# MotorShield.net
KiCad netlist of a schematic drawn in EAGLE
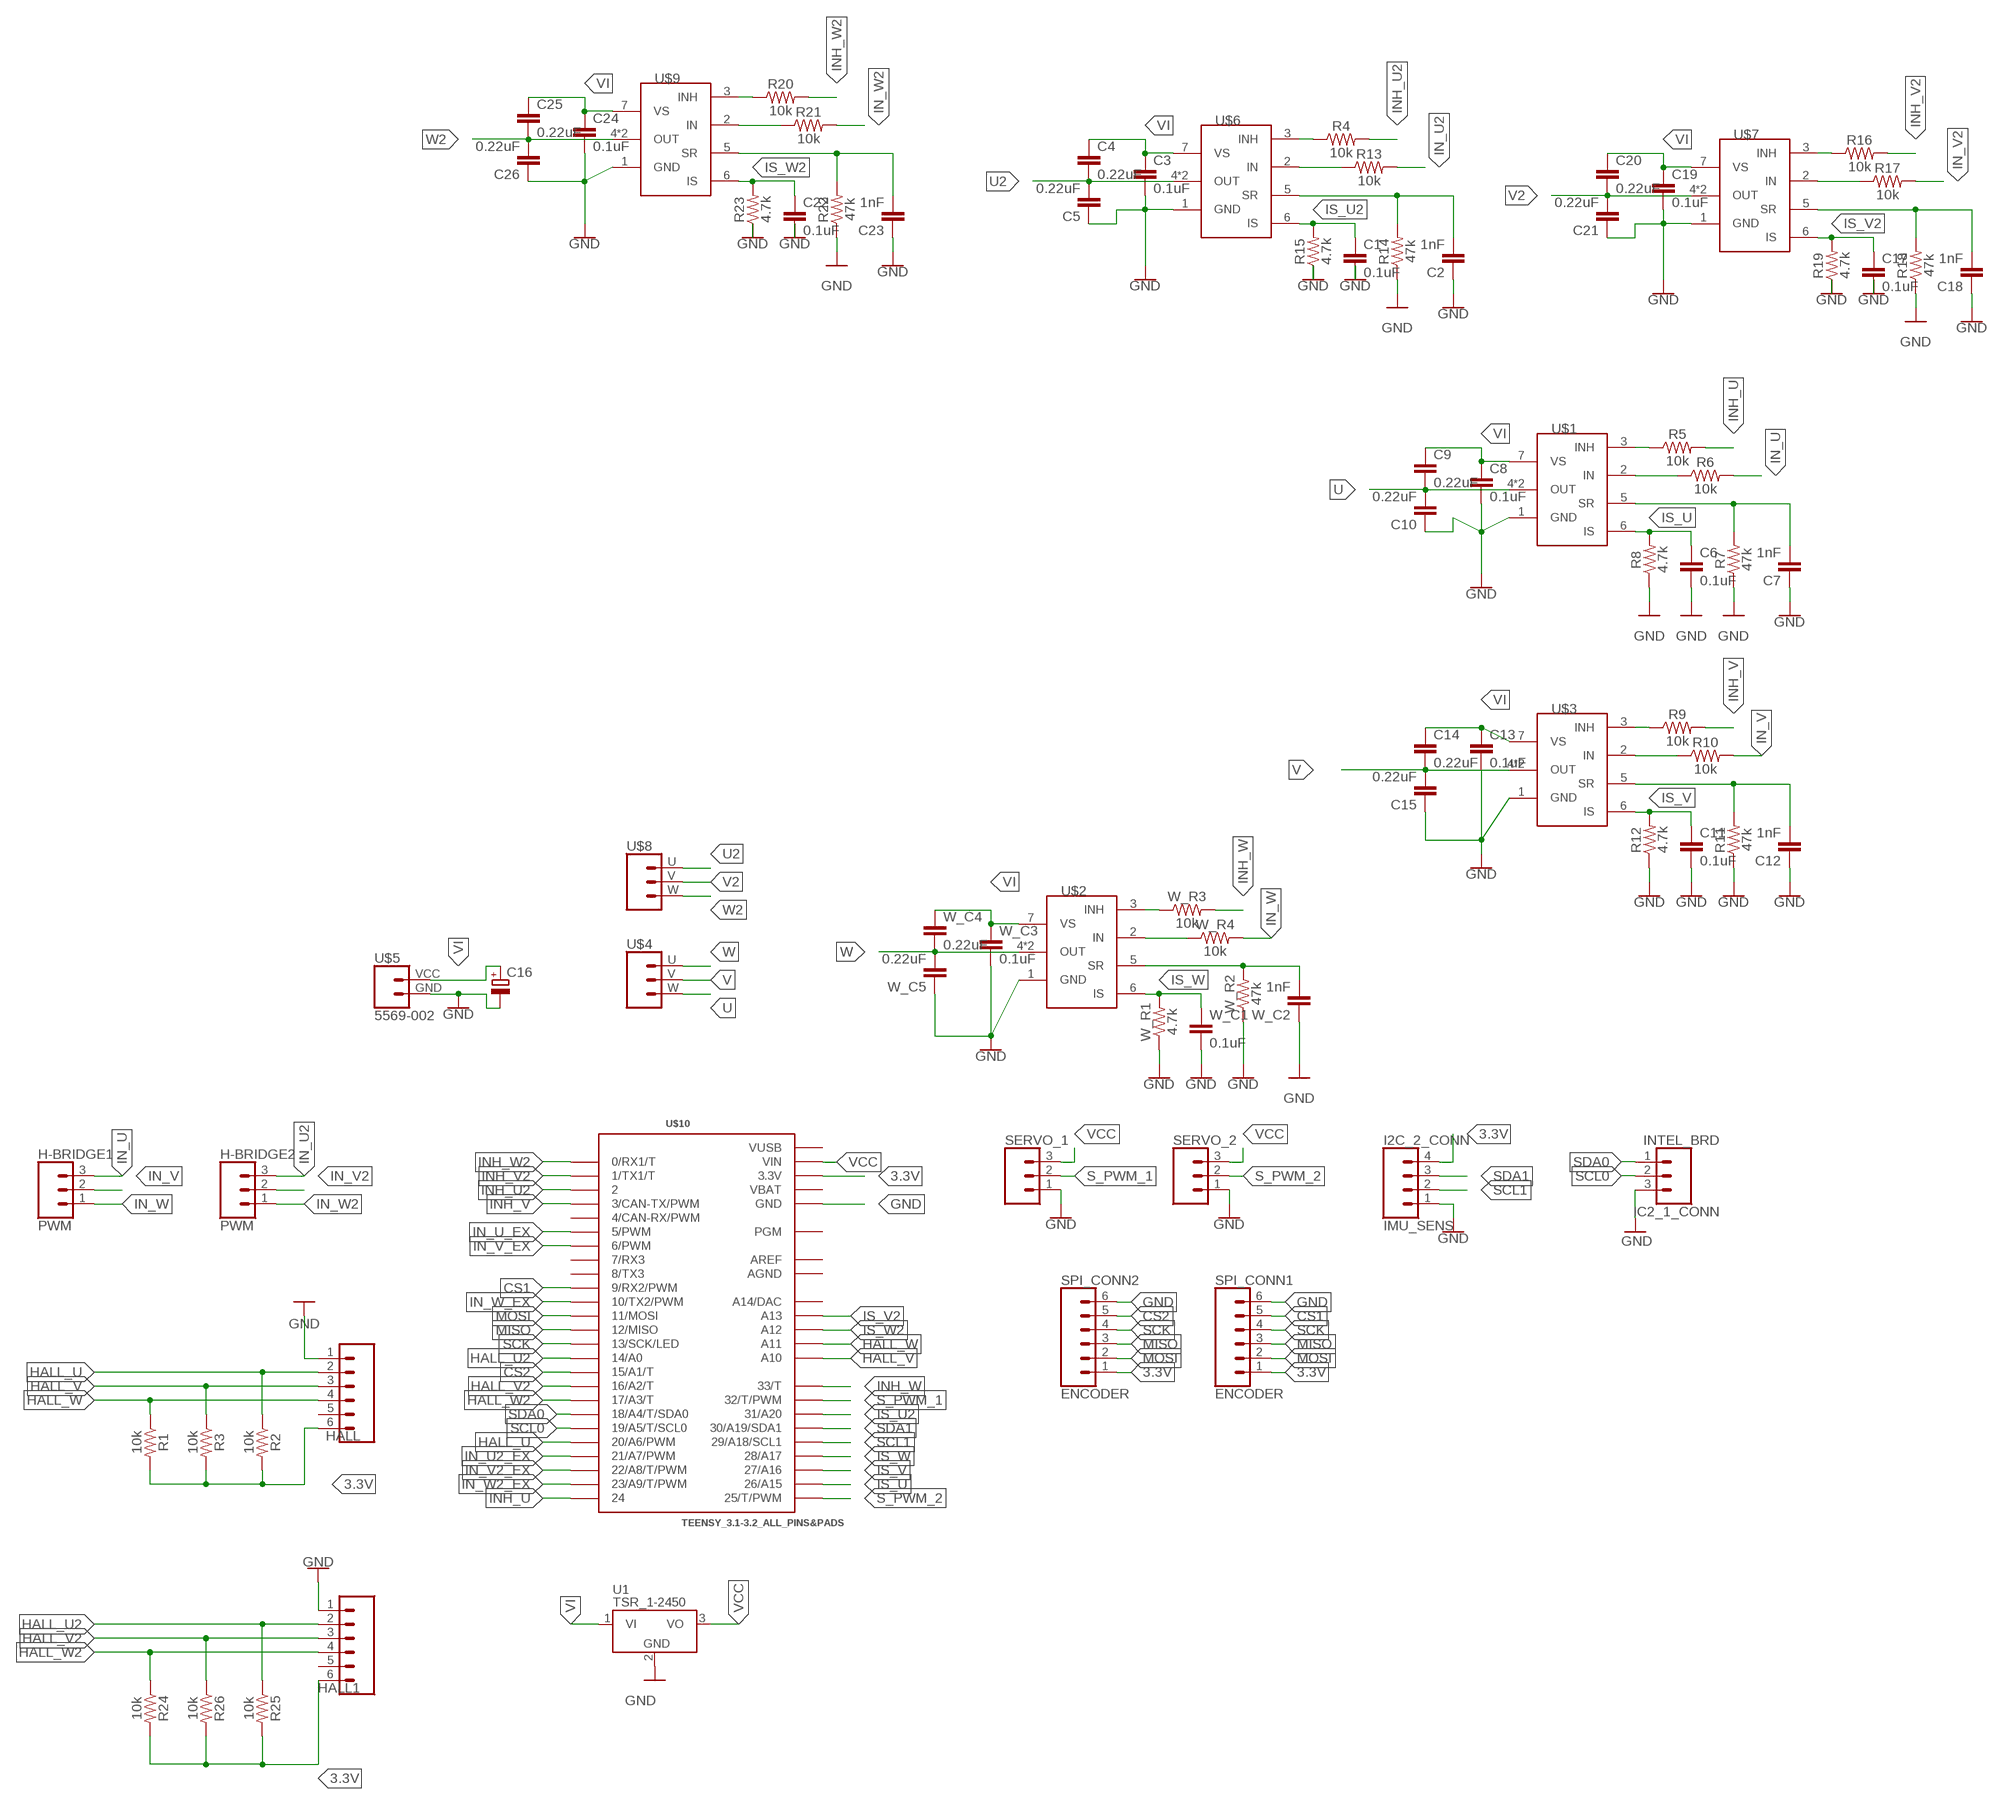
[diagram p0: schematic, sheet 1]

(export (version "E")
  (design (tool "Eeschema 10.0.6"))
  (components
    (comp (ref "C1")
      (value "0.1uF")
      (footprint "eagle-import:0603")
      (libsource (lib "eagle-import") (part "0.1UF-0603-25V-5%"))
    )
    (comp (ref "C2")
      (value "1nF")
      (footprint "eagle-import:0603")
      (libsource (lib "eagle-import") (part "1.0NF/1000PF-0603-50V-10%"))
    )
    (comp (ref "C3")
      (value "0.1uF")
      (footprint "eagle-import:0603")
      (libsource (lib "eagle-import") (part "0.1UF-0603-25V-5%"))
    )
    (comp (ref "C4")
      (value "0.22uF")
      (footprint "eagle-import:0603")
      (libsource (lib "eagle-import") (part "0.22UF-0603-25V-10%"))
    )
    (comp (ref "C5")
      (value "0.22uF")
      (footprint "eagle-import:0603")
      (libsource (lib "eagle-import") (part "0.22UF-0603-25V-10%"))
    )
    (comp (ref "C6")
      (value "0.1uF")
      (footprint "eagle-import:0603")
      (libsource (lib "eagle-import") (part "0.1UF-0603-25V-5%"))
    )
    (comp (ref "C7")
      (value "1nF")
      (footprint "eagle-import:0603")
      (libsource (lib "eagle-import") (part "1.0NF/1000PF-0603-50V-10%"))
    )
    (comp (ref "C8")
      (value "0.1uF")
      (footprint "eagle-import:0603")
      (libsource (lib "eagle-import") (part "0.1UF-0603-25V-5%"))
    )
    (comp (ref "C9")
      (value "0.22uF")
      (footprint "eagle-import:0603")
      (libsource (lib "eagle-import") (part "0.22UF-0603-25V-10%"))
    )
    (comp (ref "C10")
      (value "0.22uF")
      (footprint "eagle-import:0603")
      (libsource (lib "eagle-import") (part "0.22UF-0603-25V-10%"))
    )
    (comp (ref "C11")
      (value "0.1uF")
      (footprint "eagle-import:0603")
      (libsource (lib "eagle-import") (part "0.1UF-0603-25V-5%"))
    )
    (comp (ref "C12")
      (value "1nF")
      (footprint "eagle-import:0603")
      (libsource (lib "eagle-import") (part "1.0NF/1000PF-0603-50V-10%"))
    )
    (comp (ref "C13")
      (value "0.1uF")
      (footprint "eagle-import:0603")
      (libsource (lib "eagle-import") (part "0.1UF-0603-25V-5%"))
    )
    (comp (ref "C14")
      (value "0.22uF")
      (footprint "eagle-import:0603")
      (libsource (lib "eagle-import") (part "0.22UF-0603-25V-10%"))
    )
    (comp (ref "C15")
      (value "0.22uF")
      (footprint "eagle-import:0603")
      (libsource (lib "eagle-import") (part "0.22UF-0603-25V-10%"))
    )
    (comp (ref "C16")
      (value "CPOL-EUE2,5-6E")
      (footprint "eagle-import:E2,5-6E")
      (libsource (lib "eagle-import") (part "CPOL-EUE2,5-6E"))
    )
    (comp (ref "C17")
      (value "0.1uF")
      (footprint "eagle-import:0603")
      (libsource (lib "eagle-import") (part "0.1UF-0603-25V-5%"))
    )
    (comp (ref "C18")
      (value "1nF")
      (footprint "eagle-import:0603")
      (libsource (lib "eagle-import") (part "1.0NF/1000PF-0603-50V-10%"))
    )
    (comp (ref "C19")
      (value "0.1uF")
      (footprint "eagle-import:0603")
      (libsource (lib "eagle-import") (part "0.1UF-0603-25V-5%"))
    )
    (comp (ref "C20")
      (value "0.22uF")
      (footprint "eagle-import:0603")
      (libsource (lib "eagle-import") (part "0.22UF-0603-25V-10%"))
    )
    (comp (ref "C21")
      (value "0.22uF")
      (footprint "eagle-import:0603")
      (libsource (lib "eagle-import") (part "0.22UF-0603-25V-10%"))
    )
    (comp (ref "C22")
      (value "0.1uF")
      (footprint "eagle-import:0603")
      (libsource (lib "eagle-import") (part "0.1UF-0603-25V-5%"))
    )
    (comp (ref "C23")
      (value "1nF")
      (footprint "eagle-import:0603")
      (libsource (lib "eagle-import") (part "1.0NF/1000PF-0603-50V-10%"))
    )
    (comp (ref "C24")
      (value "0.1uF")
      (footprint "eagle-import:0603")
      (libsource (lib "eagle-import") (part "0.1UF-0603-25V-5%"))
    )
    (comp (ref "C25")
      (value "0.22uF")
      (footprint "eagle-import:0603")
      (libsource (lib "eagle-import") (part "0.22UF-0603-25V-10%"))
    )
    (comp (ref "C26")
      (value "0.22uF")
      (footprint "eagle-import:0603")
      (libsource (lib "eagle-import") (part "0.22UF-0603-25V-10%"))
    )
    (comp (ref "H-BRIDGE1")
      (value "PWM")
      (footprint "eagle-import:1X03_NO_SILK")
      (libsource (lib "eagle-import") (part "CONN_031X03_NO_SILK"))
    )
    (comp (ref "H-BRIDGE2")
      (value "PWM")
      (footprint "eagle-import:1X03_NO_SILK")
      (libsource (lib "eagle-import") (part "CONN_031X03_NO_SILK"))
    )
    (comp (ref "HALL")
      (value "CONN_06SMD-1MM")
      (footprint "eagle-import:1X06-1MM")
      (libsource (lib "eagle-import") (part "CONN_06SMD-1MM"))
    )
    (comp (ref "HALL1")
      (value "CONN_06SMD-1MM")
      (footprint "eagle-import:1X06-1MM")
      (libsource (lib "eagle-import") (part "CONN_06SMD-1MM"))
    )
    (comp (ref "I2C_2_CONN")
      (value "IMU_SENS")
      (footprint "eagle-import:1X04_NO_SILK")
      (libsource (lib "eagle-import") (part "CONN_041X04_NO_SILK"))
    )
    (comp (ref "IC2_1_CONN")
      (value "INTEL_BRD")
      (footprint "eagle-import:1X03_NO_SILK")
      (libsource (lib "eagle-import") (part "CONN_031X03_NO_SILK"))
    )
    (comp (ref "R1")
      (value "10k")
      (footprint "eagle-import:0603")
      (libsource (lib "eagle-import") (part "10KOHM-0603-1/10W-1%"))
    )
    (comp (ref "R2")
      (value "10k")
      (footprint "eagle-import:0603")
      (libsource (lib "eagle-import") (part "10KOHM-0603-1/10W-1%"))
    )
    (comp (ref "R3")
      (value "10k")
      (footprint "eagle-import:0603")
      (libsource (lib "eagle-import") (part "10KOHM-0603-1/10W-1%"))
    )
    (comp (ref "R4")
      (value "10k")
      (footprint "eagle-import:0603")
      (libsource (lib "eagle-import") (part "10KOHM-0603-1/10W-1%"))
    )
    (comp (ref "R5")
      (value "10k")
      (footprint "eagle-import:0603")
      (libsource (lib "eagle-import") (part "10KOHM-0603-1/10W-1%"))
    )
    (comp (ref "R6")
      (value "10k")
      (footprint "eagle-import:0603")
      (libsource (lib "eagle-import") (part "10KOHM-0603-1/10W-1%"))
    )
    (comp (ref "R7")
      (value "47k")
      (footprint "eagle-import:0603")
      (libsource (lib "eagle-import") (part "47KOHM-0603-1/10W-1%"))
    )
    (comp (ref "R8")
      (value "4.7k")
      (footprint "eagle-import:0603")
      (libsource (lib "eagle-import") (part "4.7KOHM-0603-1/10W-1%"))
    )
    (comp (ref "R9")
      (value "10k")
      (footprint "eagle-import:0603")
      (libsource (lib "eagle-import") (part "10KOHM-0603-1/10W-1%"))
    )
    (comp (ref "R10")
      (value "10k")
      (footprint "eagle-import:0603")
      (libsource (lib "eagle-import") (part "10KOHM-0603-1/10W-1%"))
    )
    (comp (ref "R11")
      (value "47k")
      (footprint "eagle-import:0603")
      (libsource (lib "eagle-import") (part "47KOHM-0603-1/10W-1%"))
    )
    (comp (ref "R12")
      (value "4.7k")
      (footprint "eagle-import:0603")
      (libsource (lib "eagle-import") (part "4.7KOHM-0603-1/10W-1%"))
    )
    (comp (ref "R13")
      (value "10k")
      (footprint "eagle-import:0603")
      (libsource (lib "eagle-import") (part "10KOHM-0603-1/10W-1%"))
    )
    (comp (ref "R14")
      (value "47k")
      (footprint "eagle-import:0603")
      (libsource (lib "eagle-import") (part "47KOHM-0603-1/10W-1%"))
    )
    (comp (ref "R15")
      (value "4.7k")
      (footprint "eagle-import:0603")
      (libsource (lib "eagle-import") (part "4.7KOHM-0603-1/10W-1%"))
    )
    (comp (ref "R16")
      (value "10k")
      (footprint "eagle-import:0603")
      (libsource (lib "eagle-import") (part "10KOHM-0603-1/10W-1%"))
    )
    (comp (ref "R17")
      (value "10k")
      (footprint "eagle-import:0603")
      (libsource (lib "eagle-import") (part "10KOHM-0603-1/10W-1%"))
    )
    (comp (ref "R18")
      (value "47k")
      (footprint "eagle-import:0603")
      (libsource (lib "eagle-import") (part "47KOHM-0603-1/10W-1%"))
    )
    (comp (ref "R19")
      (value "4.7k")
      (footprint "eagle-import:0603")
      (libsource (lib "eagle-import") (part "4.7KOHM-0603-1/10W-1%"))
    )
    (comp (ref "R20")
      (value "10k")
      (footprint "eagle-import:0603")
      (libsource (lib "eagle-import") (part "10KOHM-0603-1/10W-1%"))
    )
    (comp (ref "R21")
      (value "10k")
      (footprint "eagle-import:0603")
      (libsource (lib "eagle-import") (part "10KOHM-0603-1/10W-1%"))
    )
    (comp (ref "R22")
      (value "47k")
      (footprint "eagle-import:0603")
      (libsource (lib "eagle-import") (part "47KOHM-0603-1/10W-1%"))
    )
    (comp (ref "R23")
      (value "4.7k")
      (footprint "eagle-import:0603")
      (libsource (lib "eagle-import") (part "4.7KOHM-0603-1/10W-1%"))
    )
    (comp (ref "R24")
      (value "10k")
      (footprint "eagle-import:0603")
      (libsource (lib "eagle-import") (part "10KOHM-0603-1/10W-1%"))
    )
    (comp (ref "R25")
      (value "10k")
      (footprint "eagle-import:0603")
      (libsource (lib "eagle-import") (part "10KOHM-0603-1/10W-1%"))
    )
    (comp (ref "R26")
      (value "10k")
      (footprint "eagle-import:0603")
      (libsource (lib "eagle-import") (part "10KOHM-0603-1/10W-1%"))
    )
    (comp (ref "SERVO_1")
      (value "CONN_031X03_NO_SILK")
      (footprint "eagle-import:1X03_NO_SILK")
      (libsource (lib "eagle-import") (part "CONN_031X03_NO_SILK"))
    )
    (comp (ref "SERVO_2")
      (value "CONN_031X03_NO_SILK")
      (footprint "eagle-import:1X03_NO_SILK")
      (libsource (lib "eagle-import") (part "CONN_031X03_NO_SILK"))
    )
    (comp (ref "SPI_CONN1")
      (value "ENCODER")
      (footprint "eagle-import:1X06-1MM")
      (libsource (lib "eagle-import") (part "CONN_06SMD-1MM"))
    )
    (comp (ref "SPI_CONN2")
      (value "ENCODER")
      (footprint "eagle-import:1X06-1MM")
      (libsource (lib "eagle-import") (part "CONN_06SMD-1MM"))
    )
    (comp (ref "U$1")
      (value "IFX007TZZZZ")
      (footprint "eagle-import:P-TO263-7-1")
      (libsource (lib "eagle-import") (part "IFX007TZZZZ"))
    )
    (comp (ref "U$2")
      (value "IFX007TZZZZ")
      (footprint "eagle-import:P-TO263-7-1")
      (libsource (lib "eagle-import") (part "IFX007TZZZZ"))
    )
    (comp (ref "U$3")
      (value "IFX007TZZZZ")
      (footprint "eagle-import:P-TO263-7-1")
      (libsource (lib "eagle-import") (part "IFX007TZZZZ"))
    )
    (comp (ref "U$4")
      (value "5569-003")
      (footprint "eagle-import:5569-003")
      (libsource (lib "eagle-import") (part "5569-003"))
    )
    (comp (ref "U$5")
      (value "5569-002")
      (footprint "eagle-import:5569-002")
      (libsource (lib "eagle-import") (part "5569-002"))
    )
    (comp (ref "U$6")
      (value "IFX007TZZZZ")
      (footprint "eagle-import:P-TO263-7-1")
      (libsource (lib "eagle-import") (part "IFX007TZZZZ"))
    )
    (comp (ref "U$7")
      (value "IFX007TZZZZ")
      (footprint "eagle-import:P-TO263-7-1")
      (libsource (lib "eagle-import") (part "IFX007TZZZZ"))
    )
    (comp (ref "U$8")
      (value "5569-003")
      (footprint "eagle-import:5569-003")
      (libsource (lib "eagle-import") (part "5569-003"))
    )
    (comp (ref "U$9")
      (value "IFX007TZZZZ")
      (footprint "eagle-import:P-TO263-7-1")
      (libsource (lib "eagle-import") (part "IFX007TZZZZ"))
    )
    (comp (ref "U$10")
      (value "TEENSY_3.1-3.2_ALL_PINS&PADS")
      (footprint "eagle-import:TEENSY_3.0-3.2_ALL_PINS_&_PADS")
      (libsource (lib "eagle-import") (part "TEENSY_3.1-3.2_ALL_PINS&PADS"))
    )
    (comp (ref "U1")
      (value "TSR_1-2450")
      (footprint "eagle-import:TSR-1")
      (libsource (lib "eagle-import") (part "TSR_1-2450"))
    )
    (comp (ref "W_C1")
      (value "0.1uF")
      (footprint "eagle-import:0603")
      (libsource (lib "eagle-import") (part "0.1UF-0603-25V-5%"))
    )
    (comp (ref "W_C2")
      (value "1nF")
      (footprint "eagle-import:0603")
      (libsource (lib "eagle-import") (part "1.0NF/1000PF-0603-50V-10%"))
    )
    (comp (ref "W_C3")
      (value "0.1uF")
      (footprint "eagle-import:0603")
      (libsource (lib "eagle-import") (part "0.1UF-0603-25V-5%"))
    )
    (comp (ref "W_C4")
      (value "0.22uF")
      (footprint "eagle-import:0603")
      (libsource (lib "eagle-import") (part "0.22UF-0603-25V-10%"))
    )
    (comp (ref "W_C5")
      (value "0.22uF")
      (footprint "eagle-import:0603")
      (libsource (lib "eagle-import") (part "0.22UF-0603-25V-10%"))
    )
    (comp (ref "W_R1")
      (value "4.7k")
      (footprint "eagle-import:0603")
      (libsource (lib "eagle-import") (part "4.7KOHM-0603-1/10W-1%"))
    )
    (comp (ref "W_R2")
      (value "47k")
      (footprint "eagle-import:0603")
      (libsource (lib "eagle-import") (part "47KOHM-0603-1/10W-1%"))
    )
    (comp (ref "W_R3")
      (value "10k")
      (footprint "eagle-import:0603")
      (libsource (lib "eagle-import") (part "10KOHM-0603-1/10W-1%"))
    )
    (comp (ref "W_R4")
      (value "10k")
      (footprint "eagle-import:0603")
      (libsource (lib "eagle-import") (part "10KOHM-0603-1/10W-1%"))
    )
  )
  (nets
    (net (code "1") (name "/AGND") (class "Default")
      (node (ref "U$10") (pin "AGND") (pinfunction "AGND_AGND") (pintype "power_in"))
    )
    (net (code "2") (name "/AREF") (class "Default")
      (node (ref "U$10") (pin "AREF") (pinfunction "AREF_AREF") (pintype "power_in"))
    )
    (net (code "3") (name "/VBAT") (class "Default")
      (node (ref "U$10") (pin "VBAT") (pinfunction "VBAT_VBAT") (pintype "power_in"))
    )
    (net (code "4") (name "/VUSB") (class "Default")
      (node (ref "U$10") (pin "VUSB") (pinfunction "VUSB_VUSB") (pintype "power_in"))
    )
    (net (code "5") (name "3.3V") (class "Default")
      (node (ref "HALL") (pin "6") (pinfunction "6_6") (pintype "passive"))
      (node (ref "HALL1") (pin "6") (pinfunction "6_6") (pintype "passive"))
      (node (ref "I2C_2_CONN") (pin "4") (pinfunction "4_4") (pintype "passive"))
      (node (ref "R1") (pin "2") (pinfunction "2_2") (pintype "passive"))
      (node (ref "R2") (pin "2") (pinfunction "2_2") (pintype "passive"))
      (node (ref "R24") (pin "2") (pinfunction "2_2") (pintype "passive"))
      (node (ref "R25") (pin "2") (pinfunction "2_2") (pintype "passive"))
      (node (ref "R26") (pin "2") (pinfunction "2_2") (pintype "passive"))
      (node (ref "R3") (pin "2") (pinfunction "2_2") (pintype "passive"))
      (node (ref "SPI_CONN1") (pin "1") (pinfunction "1_1") (pintype "passive"))
      (node (ref "SPI_CONN2") (pin "1") (pinfunction "1_1") (pintype "passive"))
      (node (ref "U$10") (pin "3.3V") (pinfunction "3.3V_3.3V") (pintype "power_in"))
      (node (ref "U$10") (pin "3.3V1") (pinfunction "3.3V_3.3V1") (pintype "power_in"))
      (node (ref "U$10") (pin "3.3V2") (pinfunction "3.3V_3.3V2") (pintype "power_in"))
    )
    (net (code "6") (name "CS1") (class "Default")
      (node (ref "SPI_CONN1") (pin "5") (pinfunction "5_5") (pintype "passive"))
      (node (ref "U$10") (pin "9") (pinfunction "9/RX2/PWM_9") (pintype "bidirectional"))
    )
    (net (code "7") (name "CS2") (class "Default")
      (node (ref "SPI_CONN2") (pin "5") (pinfunction "5_5") (pintype "passive"))
      (node (ref "U$10") (pin "15/A1") (pinfunction "15/A1/T_15/A1") (pintype "bidirectional"))
    )
    (net (code "8") (name "GND") (class "Default")
      (node (ref "C1") (pin "2") (pinfunction "2_2") (pintype "passive"))
      (node (ref "C10") (pin "1") (pinfunction "1_1") (pintype "passive"))
      (node (ref "C11") (pin "2") (pinfunction "2_2") (pintype "passive"))
      (node (ref "C12") (pin "1") (pinfunction "1_1") (pintype "passive"))
      (node (ref "C13") (pin "2") (pinfunction "2_2") (pintype "passive"))
      (node (ref "C15") (pin "1") (pinfunction "1_1") (pintype "passive"))
      (node (ref "C16") (pin "-") (pinfunction "-_-") (pintype "passive"))
      (node (ref "C17") (pin "2") (pinfunction "2_2") (pintype "passive"))
      (node (ref "C18") (pin "1") (pinfunction "1_1") (pintype "passive"))
      (node (ref "C19") (pin "2") (pinfunction "2_2") (pintype "passive"))
      (node (ref "C2") (pin "1") (pinfunction "1_1") (pintype "passive"))
      (node (ref "C21") (pin "1") (pinfunction "1_1") (pintype "passive"))
      (node (ref "C22") (pin "2") (pinfunction "2_2") (pintype "passive"))
      (node (ref "C23") (pin "1") (pinfunction "1_1") (pintype "passive"))
      (node (ref "C24") (pin "2") (pinfunction "2_2") (pintype "passive"))
      (node (ref "C26") (pin "1") (pinfunction "1_1") (pintype "passive"))
      (node (ref "C3") (pin "2") (pinfunction "2_2") (pintype "passive"))
      (node (ref "C5") (pin "1") (pinfunction "1_1") (pintype "passive"))
      (node (ref "C6") (pin "2") (pinfunction "2_2") (pintype "passive"))
      (node (ref "C7") (pin "1") (pinfunction "1_1") (pintype "passive"))
      (node (ref "C8") (pin "2") (pinfunction "2_2") (pintype "passive"))
      (node (ref "HALL") (pin "1") (pinfunction "1_1") (pintype "passive"))
      (node (ref "HALL1") (pin "1") (pinfunction "1_1") (pintype "passive"))
      (node (ref "I2C_2_CONN") (pin "1") (pinfunction "1_1") (pintype "passive"))
      (node (ref "IC2_1_CONN") (pin "3") (pinfunction "3_3") (pintype "passive"))
      (node (ref "R11") (pin "1") (pinfunction "1_1") (pintype "passive"))
      (node (ref "R12") (pin "1") (pinfunction "1_1") (pintype "passive"))
      (node (ref "R14") (pin "1") (pinfunction "1_1") (pintype "passive"))
      (node (ref "R15") (pin "1") (pinfunction "1_1") (pintype "passive"))
      (node (ref "R18") (pin "1") (pinfunction "1_1") (pintype "passive"))
      (node (ref "R19") (pin "1") (pinfunction "1_1") (pintype "passive"))
      (node (ref "R22") (pin "1") (pinfunction "1_1") (pintype "passive"))
      (node (ref "R23") (pin "1") (pinfunction "1_1") (pintype "passive"))
      (node (ref "R7") (pin "1") (pinfunction "1_1") (pintype "passive"))
      (node (ref "R8") (pin "1") (pinfunction "1_1") (pintype "passive"))
      (node (ref "SERVO_1") (pin "1") (pinfunction "1_1") (pintype "passive"))
      (node (ref "SERVO_2") (pin "1") (pinfunction "1_1") (pintype "passive"))
      (node (ref "SPI_CONN1") (pin "6") (pinfunction "6_6") (pintype "passive"))
      (node (ref "SPI_CONN2") (pin "6") (pinfunction "6_6") (pintype "passive"))
      (node (ref "U$1") (pin "1") (pinfunction "GND_1") (pintype "power_in"))
      (node (ref "U$10") (pin "GND") (pinfunction "GND_GND") (pintype "power_in"))
      (node (ref "U$10") (pin "GND1") (pinfunction "GND_GND1") (pintype "power_in"))
      (node (ref "U$10") (pin "GND2") (pinfunction "GND_GND2") (pintype "power_in"))
      (node (ref "U$2") (pin "1") (pinfunction "GND_1") (pintype "power_in"))
      (node (ref "U$3") (pin "1") (pinfunction "GND_1") (pintype "power_in"))
      (node (ref "U$5") (pin "GND") (pinfunction "1_GND") (pintype "passive"))
      (node (ref "U$6") (pin "1") (pinfunction "GND_1") (pintype "power_in"))
      (node (ref "U$7") (pin "1") (pinfunction "GND_1") (pintype "power_in"))
      (node (ref "U$9") (pin "1") (pinfunction "GND_1") (pintype "power_in"))
      (node (ref "U1") (pin "2") (pinfunction "GND_2") (pintype "power_in"))
      (node (ref "W_C1") (pin "2") (pinfunction "2_2") (pintype "passive"))
      (node (ref "W_C2") (pin "1") (pinfunction "1_1") (pintype "passive"))
      (node (ref "W_C3") (pin "2") (pinfunction "2_2") (pintype "passive"))
      (node (ref "W_C5") (pin "1") (pinfunction "1_1") (pintype "passive"))
      (node (ref "W_R1") (pin "1") (pinfunction "1_1") (pintype "passive"))
      (node (ref "W_R2") (pin "1") (pinfunction "1_1") (pintype "passive"))
    )
    (net (code "9") (name "HALL_U") (class "Default")
      (node (ref "HALL") (pin "2") (pinfunction "2_2") (pintype "passive"))
      (node (ref "R2") (pin "1") (pinfunction "1_1") (pintype "passive"))
      (node (ref "U$10") (pin "20/A6") (pinfunction "20/A6/PWM_20/A6") (pintype "bidirectional"))
    )
    (net (code "10") (name "HALL_U2") (class "Default")
      (node (ref "HALL1") (pin "2") (pinfunction "2_2") (pintype "passive"))
      (node (ref "R25") (pin "1") (pinfunction "1_1") (pintype "passive"))
      (node (ref "U$10") (pin "14/A0") (pinfunction "14/A0_14/A0") (pintype "bidirectional"))
    )
    (net (code "11") (name "HALL_V") (class "Default")
      (node (ref "HALL") (pin "3") (pinfunction "3_3") (pintype "passive"))
      (node (ref "R3") (pin "1") (pinfunction "1_1") (pintype "passive"))
      (node (ref "U$10") (pin "A10") (pinfunction "A10_A10") (pintype "bidirectional"))
    )
    (net (code "12") (name "HALL_V2") (class "Default")
      (node (ref "HALL1") (pin "3") (pinfunction "3_3") (pintype "passive"))
      (node (ref "R26") (pin "1") (pinfunction "1_1") (pintype "passive"))
      (node (ref "U$10") (pin "16/A2") (pinfunction "16/A2/T_16/A2") (pintype "bidirectional"))
    )
    (net (code "13") (name "HALL_W") (class "Default")
      (node (ref "HALL") (pin "4") (pinfunction "4_4") (pintype "passive"))
      (node (ref "R1") (pin "1") (pinfunction "1_1") (pintype "passive"))
      (node (ref "U$10") (pin "A11") (pinfunction "A11_A11") (pintype "bidirectional"))
    )
    (net (code "14") (name "HALL_W2") (class "Default")
      (node (ref "HALL1") (pin "4") (pinfunction "4_4") (pintype "passive"))
      (node (ref "R24") (pin "1") (pinfunction "1_1") (pintype "passive"))
      (node (ref "U$10") (pin "17/A3") (pinfunction "17/A3/T_17/A3") (pintype "bidirectional"))
    )
    (net (code "15") (name "INH_U") (class "Default")
      (node (ref "R5") (pin "2") (pinfunction "2_2") (pintype "passive"))
      (node (ref "U$10") (pin "24") (pinfunction "24_24") (pintype "bidirectional"))
    )
    (net (code "16") (name "INH_U2") (class "Default")
      (node (ref "R4") (pin "2") (pinfunction "2_2") (pintype "passive"))
      (node (ref "U$10") (pin "2") (pinfunction "2_2") (pintype "bidirectional"))
    )
    (net (code "17") (name "INH_V") (class "Default")
      (node (ref "R9") (pin "2") (pinfunction "2_2") (pintype "passive"))
      (node (ref "U$10") (pin "3") (pinfunction "3/CAN-TX/PWM_3") (pintype "bidirectional"))
    )
    (net (code "18") (name "INH_V2") (class "Default")
      (node (ref "R16") (pin "2") (pinfunction "2_2") (pintype "passive"))
      (node (ref "U$10") (pin "1") (pinfunction "1/TX1/T_1") (pintype "bidirectional"))
    )
    (net (code "19") (name "INH_W") (class "Default")
      (node (ref "U$10") (pin "33") (pinfunction "33/T_33") (pintype "bidirectional"))
      (node (ref "W_R3") (pin "2") (pinfunction "2_2") (pintype "passive"))
    )
    (net (code "20") (name "INH_W2") (class "Default")
      (node (ref "R20") (pin "2") (pinfunction "2_2") (pintype "passive"))
      (node (ref "U$10") (pin "0") (pinfunction "0/RX1/T_0") (pintype "bidirectional"))
    )
    (net (code "21") (name "IN_U") (class "Default")
      (node (ref "H-BRIDGE1") (pin "3") (pinfunction "3_3") (pintype "passive"))
      (node (ref "R6") (pin "2") (pinfunction "2_2") (pintype "passive"))
    )
    (net (code "22") (name "IN_U2") (class "Default")
      (node (ref "H-BRIDGE2") (pin "3") (pinfunction "3_3") (pintype "passive"))
      (node (ref "R13") (pin "2") (pinfunction "2_2") (pintype "passive"))
    )
    (net (code "23") (name "IN_U2_EX") (class "Default")
      (node (ref "U$10") (pin "21/A7") (pinfunction "21/A7/PWM_21/A7") (pintype "bidirectional"))
    )
    (net (code "24") (name "IN_U_EX") (class "Default")
      (node (ref "U$10") (pin "5") (pinfunction "5/PWM_5") (pintype "bidirectional"))
    )
    (net (code "25") (name "IN_V") (class "Default")
      (node (ref "H-BRIDGE1") (pin "2") (pinfunction "2_2") (pintype "passive"))
      (node (ref "R10") (pin "2") (pinfunction "2_2") (pintype "passive"))
    )
    (net (code "26") (name "IN_V2") (class "Default")
      (node (ref "H-BRIDGE2") (pin "2") (pinfunction "2_2") (pintype "passive"))
      (node (ref "R17") (pin "2") (pinfunction "2_2") (pintype "passive"))
    )
    (net (code "27") (name "IN_V2_EX") (class "Default")
      (node (ref "U$10") (pin "22/A8") (pinfunction "22/A8/T/PWM_22/A8") (pintype "bidirectional"))
    )
    (net (code "28") (name "IN_V_EX") (class "Default")
      (node (ref "U$10") (pin "6") (pinfunction "6/PWM_6") (pintype "bidirectional"))
    )
    (net (code "29") (name "IN_W") (class "Default")
      (node (ref "H-BRIDGE1") (pin "1") (pinfunction "1_1") (pintype "passive"))
      (node (ref "W_R4") (pin "2") (pinfunction "2_2") (pintype "passive"))
    )
    (net (code "30") (name "IN_W2") (class "Default")
      (node (ref "H-BRIDGE2") (pin "1") (pinfunction "1_1") (pintype "passive"))
      (node (ref "R21") (pin "2") (pinfunction "2_2") (pintype "passive"))
    )
    (net (code "31") (name "IN_W2_EX") (class "Default")
      (node (ref "U$10") (pin "23/A9") (pinfunction "23/A9/T/PWM_23/A9") (pintype "bidirectional"))
    )
    (net (code "32") (name "IN_W_EX") (class "Default")
      (node (ref "U$10") (pin "10") (pinfunction "10/TX2/PWM_10") (pintype "bidirectional"))
    )
    (net (code "33") (name "IS_U") (class "Default")
      (node (ref "C6") (pin "1") (pinfunction "1_1") (pintype "passive"))
      (node (ref "R8") (pin "2") (pinfunction "2_2") (pintype "passive"))
      (node (ref "U$1") (pin "6") (pinfunction "IS_6") (pintype "output"))
      (node (ref "U$10") (pin "26") (pinfunction "26/A15_26") (pintype "bidirectional"))
    )
    (net (code "34") (name "IS_U2") (class "Default")
      (node (ref "C1") (pin "1") (pinfunction "1_1") (pintype "passive"))
      (node (ref "R15") (pin "2") (pinfunction "2_2") (pintype "passive"))
      (node (ref "U$10") (pin "31") (pinfunction "31/A20_31") (pintype "bidirectional"))
      (node (ref "U$6") (pin "6") (pinfunction "IS_6") (pintype "output"))
    )
    (net (code "35") (name "IS_V") (class "Default")
      (node (ref "C11") (pin "1") (pinfunction "1_1") (pintype "passive"))
      (node (ref "R12") (pin "2") (pinfunction "2_2") (pintype "passive"))
      (node (ref "U$10") (pin "27") (pinfunction "27/A16_27") (pintype "bidirectional"))
      (node (ref "U$3") (pin "6") (pinfunction "IS_6") (pintype "output"))
    )
    (net (code "36") (name "IS_V2") (class "Default")
      (node (ref "C17") (pin "1") (pinfunction "1_1") (pintype "passive"))
      (node (ref "R19") (pin "2") (pinfunction "2_2") (pintype "passive"))
      (node (ref "U$10") (pin "A13") (pinfunction "A13_A13") (pintype "bidirectional"))
      (node (ref "U$7") (pin "6") (pinfunction "IS_6") (pintype "output"))
    )
    (net (code "37") (name "IS_W") (class "Default")
      (node (ref "U$10") (pin "28") (pinfunction "28/A17_28") (pintype "bidirectional"))
      (node (ref "U$2") (pin "6") (pinfunction "IS_6") (pintype "output"))
      (node (ref "W_C1") (pin "1") (pinfunction "1_1") (pintype "passive"))
      (node (ref "W_R1") (pin "2") (pinfunction "2_2") (pintype "passive"))
    )
    (net (code "38") (name "IS_W2") (class "Default")
      (node (ref "C22") (pin "1") (pinfunction "1_1") (pintype "passive"))
      (node (ref "R23") (pin "2") (pinfunction "2_2") (pintype "passive"))
      (node (ref "U$10") (pin "A12") (pinfunction "A12_A12") (pintype "bidirectional"))
      (node (ref "U$9") (pin "6") (pinfunction "IS_6") (pintype "output"))
    )
    (net (code "39") (name "MISO") (class "Default")
      (node (ref "SPI_CONN1") (pin "3") (pinfunction "3_3") (pintype "passive"))
      (node (ref "SPI_CONN2") (pin "3") (pinfunction "3_3") (pintype "passive"))
      (node (ref "U$10") (pin "12") (pinfunction "12/MISO_12") (pintype "bidirectional"))
    )
    (net (code "40") (name "MOSI") (class "Default")
      (node (ref "SPI_CONN1") (pin "2") (pinfunction "2_2") (pintype "passive"))
      (node (ref "SPI_CONN2") (pin "2") (pinfunction "2_2") (pintype "passive"))
      (node (ref "U$10") (pin "11") (pinfunction "11/MOSI_11") (pintype "bidirectional"))
    )
    (net (code "41") (name "Net-(U$1-IN)") (class "Default")
      (node (ref "R6") (pin "1") (pinfunction "1_1") (pintype "passive"))
      (node (ref "U$1") (pin "2") (pinfunction "IN_2") (pintype "input"))
    )
    (net (code "42") (name "Net-(U$1-INH)") (class "Default")
      (node (ref "R5") (pin "1") (pinfunction "1_1") (pintype "passive"))
      (node (ref "U$1") (pin "3") (pinfunction "INH_3") (pintype "bidirectional"))
    )
    (net (code "43") (name "Net-(U$1-SR)") (class "Default")
      (node (ref "C7") (pin "2") (pinfunction "2_2") (pintype "passive"))
      (node (ref "R7") (pin "2") (pinfunction "2_2") (pintype "passive"))
      (node (ref "U$1") (pin "5") (pinfunction "SR_5") (pintype "input"))
    )
    (net (code "44") (name "Net-(U$2-IN)") (class "Default")
      (node (ref "U$2") (pin "2") (pinfunction "IN_2") (pintype "input"))
      (node (ref "W_R4") (pin "1") (pinfunction "1_1") (pintype "passive"))
    )
    (net (code "45") (name "Net-(U$2-INH)") (class "Default")
      (node (ref "U$2") (pin "3") (pinfunction "INH_3") (pintype "bidirectional"))
      (node (ref "W_R3") (pin "1") (pinfunction "1_1") (pintype "passive"))
    )
    (net (code "46") (name "Net-(U$2-SR)") (class "Default")
      (node (ref "U$2") (pin "5") (pinfunction "SR_5") (pintype "input"))
      (node (ref "W_C2") (pin "2") (pinfunction "2_2") (pintype "passive"))
      (node (ref "W_R2") (pin "2") (pinfunction "2_2") (pintype "passive"))
    )
    (net (code "47") (name "Net-(U$3-IN)") (class "Default")
      (node (ref "R10") (pin "1") (pinfunction "1_1") (pintype "passive"))
      (node (ref "U$3") (pin "2") (pinfunction "IN_2") (pintype "input"))
    )
    (net (code "48") (name "Net-(U$3-INH)") (class "Default")
      (node (ref "R9") (pin "1") (pinfunction "1_1") (pintype "passive"))
      (node (ref "U$3") (pin "3") (pinfunction "INH_3") (pintype "bidirectional"))
    )
    (net (code "49") (name "Net-(U$3-SR)") (class "Default")
      (node (ref "C12") (pin "2") (pinfunction "2_2") (pintype "passive"))
      (node (ref "R11") (pin "2") (pinfunction "2_2") (pintype "passive"))
      (node (ref "U$3") (pin "5") (pinfunction "SR_5") (pintype "input"))
    )
    (net (code "50") (name "Net-(U$6-IN)") (class "Default")
      (node (ref "R13") (pin "1") (pinfunction "1_1") (pintype "passive"))
      (node (ref "U$6") (pin "2") (pinfunction "IN_2") (pintype "input"))
    )
    (net (code "51") (name "Net-(U$6-INH)") (class "Default")
      (node (ref "R4") (pin "1") (pinfunction "1_1") (pintype "passive"))
      (node (ref "U$6") (pin "3") (pinfunction "INH_3") (pintype "bidirectional"))
    )
    (net (code "52") (name "Net-(U$6-SR)") (class "Default")
      (node (ref "C2") (pin "2") (pinfunction "2_2") (pintype "passive"))
      (node (ref "R14") (pin "2") (pinfunction "2_2") (pintype "passive"))
      (node (ref "U$6") (pin "5") (pinfunction "SR_5") (pintype "input"))
    )
    (net (code "53") (name "Net-(U$7-IN)") (class "Default")
      (node (ref "R17") (pin "1") (pinfunction "1_1") (pintype "passive"))
      (node (ref "U$7") (pin "2") (pinfunction "IN_2") (pintype "input"))
    )
    (net (code "54") (name "Net-(U$7-INH)") (class "Default")
      (node (ref "R16") (pin "1") (pinfunction "1_1") (pintype "passive"))
      (node (ref "U$7") (pin "3") (pinfunction "INH_3") (pintype "bidirectional"))
    )
    (net (code "55") (name "Net-(U$7-SR)") (class "Default")
      (node (ref "C18") (pin "2") (pinfunction "2_2") (pintype "passive"))
      (node (ref "R18") (pin "2") (pinfunction "2_2") (pintype "passive"))
      (node (ref "U$7") (pin "5") (pinfunction "SR_5") (pintype "input"))
    )
    (net (code "56") (name "Net-(U$9-IN)") (class "Default")
      (node (ref "R21") (pin "1") (pinfunction "1_1") (pintype "passive"))
      (node (ref "U$9") (pin "2") (pinfunction "IN_2") (pintype "input"))
    )
    (net (code "57") (name "Net-(U$9-INH)") (class "Default")
      (node (ref "R20") (pin "1") (pinfunction "1_1") (pintype "passive"))
      (node (ref "U$9") (pin "3") (pinfunction "INH_3") (pintype "bidirectional"))
    )
    (net (code "58") (name "Net-(U$9-SR)") (class "Default")
      (node (ref "C23") (pin "2") (pinfunction "2_2") (pintype "passive"))
      (node (ref "R22") (pin "2") (pinfunction "2_2") (pintype "passive"))
      (node (ref "U$9") (pin "5") (pinfunction "SR_5") (pintype "input"))
    )
    (net (code "59") (name "SCK") (class "Default")
      (node (ref "SPI_CONN1") (pin "4") (pinfunction "4_4") (pintype "passive"))
      (node (ref "SPI_CONN2") (pin "4") (pinfunction "4_4") (pintype "passive"))
      (node (ref "U$10") (pin "13") (pinfunction "13/SCK/LED_13") (pintype "bidirectional"))
    )
    (net (code "60") (name "SCL0") (class "Default")
      (node (ref "IC2_1_CONN") (pin "2") (pinfunction "2_2") (pintype "passive"))
      (node (ref "U$10") (pin "19/A5") (pinfunction "19/A5/T/SCL0_19/A5") (pintype "bidirectional"))
    )
    (net (code "61") (name "SCL1") (class "Default")
      (node (ref "I2C_2_CONN") (pin "2") (pinfunction "2_2") (pintype "passive"))
      (node (ref "U$10") (pin "29") (pinfunction "29/A18/SCL1_29") (pintype "bidirectional"))
    )
    (net (code "62") (name "SDA0") (class "Default")
      (node (ref "IC2_1_CONN") (pin "1") (pinfunction "1_1") (pintype "passive"))
      (node (ref "U$10") (pin "18/A4") (pinfunction "18/A4/T/SDA0_18/A4") (pintype "bidirectional"))
    )
    (net (code "63") (name "SDA1") (class "Default")
      (node (ref "I2C_2_CONN") (pin "3") (pinfunction "3_3") (pintype "passive"))
      (node (ref "U$10") (pin "30") (pinfunction "30/A19/SDA1_30") (pintype "bidirectional"))
    )
    (net (code "64") (name "S_PWM_1") (class "Default")
      (node (ref "SERVO_1") (pin "2") (pinfunction "2_2") (pintype "passive"))
      (node (ref "U$10") (pin "32") (pinfunction "32/T/PWM_32") (pintype "bidirectional"))
    )
    (net (code "65") (name "S_PWM_2") (class "Default")
      (node (ref "SERVO_2") (pin "2") (pinfunction "2_2") (pintype "passive"))
      (node (ref "U$10") (pin "25") (pinfunction "25/T/PWM_25") (pintype "bidirectional"))
    )
    (net (code "66") (name "U") (class "Default")
      (node (ref "C10") (pin "2") (pinfunction "2_2") (pintype "passive"))
      (node (ref "C9") (pin "2") (pinfunction "2_2") (pintype "passive"))
      (node (ref "U$1") (pin "4") (pinfunction "OUT_4") (pintype "power_in"))
      (node (ref "U$1") (pin "8") (pinfunction "OUT_8") (pintype "power_in"))
      (node (ref "U$4") (pin "W") (pinfunction "V_W") (pintype "passive"))
    )
    (net (code "67") (name "U2") (class "Default")
      (node (ref "C4") (pin "2") (pinfunction "2_2") (pintype "passive"))
      (node (ref "C5") (pin "2") (pinfunction "2_2") (pintype "passive"))
      (node (ref "U$6") (pin "4") (pinfunction "OUT_4") (pintype "power_in"))
      (node (ref "U$6") (pin "8") (pinfunction "OUT_8") (pintype "power_in"))
      (node (ref "U$8") (pin "U") (pinfunction "W_U") (pintype "passive"))
    )
    (net (code "68") (name "V") (class "Default")
      (node (ref "C14") (pin "2") (pinfunction "2_2") (pintype "passive"))
      (node (ref "C15") (pin "2") (pinfunction "2_2") (pintype "passive"))
      (node (ref "U$3") (pin "4") (pinfunction "OUT_4") (pintype "power_in"))
      (node (ref "U$3") (pin "8") (pinfunction "OUT_8") (pintype "power_in"))
      (node (ref "U$4") (pin "V") (pinfunction "U_V") (pintype "passive"))
    )
    (net (code "69") (name "V2") (class "Default")
      (node (ref "C20") (pin "2") (pinfunction "2_2") (pintype "passive"))
      (node (ref "C21") (pin "2") (pinfunction "2_2") (pintype "passive"))
      (node (ref "U$7") (pin "4") (pinfunction "OUT_4") (pintype "power_in"))
      (node (ref "U$7") (pin "8") (pinfunction "OUT_8") (pintype "power_in"))
      (node (ref "U$8") (pin "V") (pinfunction "U_V") (pintype "passive"))
    )
    (net (code "70") (name "VCC") (class "Default")
      (node (ref "SERVO_1") (pin "3") (pinfunction "3_3") (pintype "passive"))
      (node (ref "SERVO_2") (pin "3") (pinfunction "3_3") (pintype "passive"))
      (node (ref "U$10") (pin "VIN") (pinfunction "VIN_VIN") (pintype "power_in"))
      (node (ref "U1") (pin "3") (pinfunction "VO_3") (pintype "power_in"))
    )
    (net (code "71") (name "VI") (class "Default")
      (node (ref "C13") (pin "1") (pinfunction "1_1") (pintype "passive"))
      (node (ref "C14") (pin "1") (pinfunction "1_1") (pintype "passive"))
      (node (ref "C16") (pin "+") (pinfunction "+_+") (pintype "passive"))
      (node (ref "C19") (pin "1") (pinfunction "1_1") (pintype "passive"))
      (node (ref "C20") (pin "1") (pinfunction "1_1") (pintype "passive"))
      (node (ref "C24") (pin "1") (pinfunction "1_1") (pintype "passive"))
      (node (ref "C25") (pin "1") (pinfunction "1_1") (pintype "passive"))
      (node (ref "C3") (pin "1") (pinfunction "1_1") (pintype "passive"))
      (node (ref "C4") (pin "1") (pinfunction "1_1") (pintype "passive"))
      (node (ref "C8") (pin "1") (pinfunction "1_1") (pintype "passive"))
      (node (ref "C9") (pin "1") (pinfunction "1_1") (pintype "passive"))
      (node (ref "U$1") (pin "7") (pinfunction "VS_7") (pintype "power_in"))
      (node (ref "U$2") (pin "7") (pinfunction "VS_7") (pintype "power_in"))
      (node (ref "U$3") (pin "7") (pinfunction "VS_7") (pintype "power_in"))
      (node (ref "U$5") (pin "VCC") (pinfunction "2_VCC") (pintype "passive"))
      (node (ref "U$6") (pin "7") (pinfunction "VS_7") (pintype "power_in"))
      (node (ref "U$7") (pin "7") (pinfunction "VS_7") (pintype "power_in"))
      (node (ref "U$9") (pin "7") (pinfunction "VS_7") (pintype "power_in"))
      (node (ref "U1") (pin "1") (pinfunction "VI_1") (pintype "power_in"))
      (node (ref "W_C3") (pin "1") (pinfunction "1_1") (pintype "passive"))
      (node (ref "W_C4") (pin "1") (pinfunction "1_1") (pintype "passive"))
    )
    (net (code "72") (name "W") (class "Default")
      (node (ref "U$2") (pin "4") (pinfunction "OUT_4") (pintype "power_in"))
      (node (ref "U$2") (pin "8") (pinfunction "OUT_8") (pintype "power_in"))
      (node (ref "U$4") (pin "U") (pinfunction "W_U") (pintype "passive"))
      (node (ref "W_C4") (pin "2") (pinfunction "2_2") (pintype "passive"))
      (node (ref "W_C5") (pin "2") (pinfunction "2_2") (pintype "passive"))
    )
    (net (code "73") (name "W2") (class "Default")
      (node (ref "C25") (pin "2") (pinfunction "2_2") (pintype "passive"))
      (node (ref "C26") (pin "2") (pinfunction "2_2") (pintype "passive"))
      (node (ref "U$8") (pin "W") (pinfunction "V_W") (pintype "passive"))
      (node (ref "U$9") (pin "4") (pinfunction "OUT_4") (pintype "power_in"))
      (node (ref "U$9") (pin "8") (pinfunction "OUT_8") (pintype "power_in"))
    )
    (net (code "74") (name "unconnected-(HALL-Pad5)") (class "Default")
      (node (ref "HALL") (pin "5") (pinfunction "5_5") (pintype "passive"))
    )
    (net (code "75") (name "unconnected-(HALL1-Pad5)") (class "Default")
      (node (ref "HALL1") (pin "5") (pinfunction "5_5") (pintype "passive"))
    )
    (net (code "76") (name "unconnected-(U$10-4{slash}CAN-RX{slash}PWM-Pad4)") (class "Default")
      (node (ref "U$10") (pin "4") (pinfunction "4/CAN-RX/PWM_4") (pintype "bidirectional"))
    )
    (net (code "77") (name "unconnected-(U$10-7{slash}RX3-Pad7)") (class "Default")
      (node (ref "U$10") (pin "7") (pinfunction "7/RX3_7") (pintype "bidirectional"))
    )
    (net (code "78") (name "unconnected-(U$10-8{slash}TX3-Pad8)") (class "Default")
      (node (ref "U$10") (pin "8") (pinfunction "8/TX3_8") (pintype "bidirectional"))
    )
    (net (code "79") (name "unconnected-(U$10-A14{slash}DAC-PadRESET{slash}DAC)") (class "Default")
      (node (ref "U$10") (pin "RESET/DAC") (pinfunction "A14/DAC_RESET/DAC") (pintype "bidirectional"))
    )
    (net (code "80") (name "unconnected-(U$10-PadPGM)") (class "Default")
      (node (ref "U$10") (pin "PGM") (pinfunction "PGM_PGM") (pintype "bidirectional"))
    )
  )
)
